# streamr_math_nap.net
KiCad netlist of a schematic drawn in EAGLE
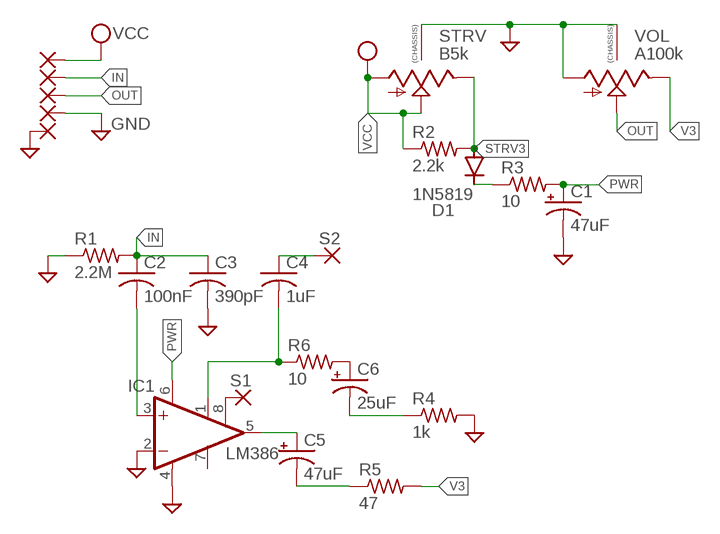
[diagram p0: schematic, sheet 1]

(export (version "E")
  (design (tool "Eeschema 10.0.6"))
  (components
    (comp (ref "C1")
      (value "47uF")
      (footprint "eagle-import:PAN_C_SMD+THRU")
      (libsource (lib "eagle-import") (part "CAP_SMD+THRUPAN_C"))
    )
    (comp (ref "C2")
      (value "100nF")
      (footprint "eagle-import:C0805")
      (libsource (lib "eagle-import") (part "C-USC0805"))
    )
    (comp (ref "C3")
      (value "390pF")
      (footprint "eagle-import:C0805")
      (libsource (lib "eagle-import") (part "C-USC0805"))
    )
    (comp (ref "C4")
      (value "1uF")
      (footprint "eagle-import:C0805")
      (libsource (lib "eagle-import") (part "C-USC0805"))
    )
    (comp (ref "C5")
      (value "47uF")
      (footprint "eagle-import:PAN_C_SMD+THRU")
      (libsource (lib "eagle-import") (part "CAP_SMD+THRUPAN_C"))
    )
    (comp (ref "C6")
      (value "25uF")
      (footprint "eagle-import:PAN_C_SMD+THRU")
      (libsource (lib "eagle-import") (part "CAP_SMD+THRUPAN_C"))
    )
    (comp (ref "D1")
      (value "1N5819")
      (footprint "eagle-import:SOD123")
      (libsource (lib "eagle-import") (part "DIODE-SOD123"))
    )
    (comp (ref "IC1")
      (value "LM386")
      (footprint "eagle-import:SO08")
      (libsource (lib "eagle-import") (part "LM386?-M1"))
    )
    (comp (ref "PAD1")
      (value "1,6/0,8")
      (footprint "eagle-import:1,6_0,8")
      (libsource (lib "eagle-import") (part "1,6/0,8"))
    )
    (comp (ref "PAD2")
      (value "1,6/0,8")
      (footprint "eagle-import:1,6_0,8")
      (libsource (lib "eagle-import") (part "1,6/0,8"))
    )
    (comp (ref "PAD3")
      (value "1,6/0,8")
      (footprint "eagle-import:1,6_0,8")
      (libsource (lib "eagle-import") (part "1,6/0,8"))
    )
    (comp (ref "PAD4")
      (value "1,6/0,8")
      (footprint "eagle-import:1,6_0,8")
      (libsource (lib "eagle-import") (part "1,6/0,8"))
    )
    (comp (ref "PAD5")
      (value "1,6/0,8")
      (footprint "eagle-import:1,6_0,8")
      (libsource (lib "eagle-import") (part "1,6/0,8"))
    )
    (comp (ref "R1")
      (value "2.2M")
      (footprint "eagle-import:R0805")
      (libsource (lib "eagle-import") (part "R-US_R0805"))
    )
    (comp (ref "R2")
      (value "2.2k")
      (footprint "eagle-import:R1206")
      (libsource (lib "eagle-import") (part "R-US_R1206"))
    )
    (comp (ref "R3")
      (value "10")
      (footprint "eagle-import:R1206")
      (libsource (lib "eagle-import") (part "R-US_R1206"))
    )
    (comp (ref "R4")
      (value "1k")
      (footprint "eagle-import:R1206")
      (libsource (lib "eagle-import") (part "R-US_R1206"))
    )
    (comp (ref "R5")
      (value "47")
      (footprint "eagle-import:R1206")
      (libsource (lib "eagle-import") (part "R-US_R1206"))
    )
    (comp (ref "R6")
      (value "10")
      (footprint "eagle-import:R1206")
      (libsource (lib "eagle-import") (part "R-US_R1206"))
    )
    (comp (ref "S1")
      (value "S1")
      (footprint "eagle-import:1,6_0,8")
      (libsource (lib "eagle-import") (part "1,6/0,8"))
    )
    (comp (ref "S2")
      (value "S2")
      (footprint "eagle-import:1,6_0,8")
      (libsource (lib "eagle-import") (part "1,6/0,8"))
    )
    (comp (ref "STRV")
      (value "B5k")
      (footprint "eagle-import:9MM_SNAP-IN_POT")
      (libsource (lib "eagle-import") (part "9MM_SNAP-IN_POT_CHASSIS"))
    )
    (comp (ref "VOL")
      (value "A100k")
      (footprint "eagle-import:9MM_SNAP-IN_POT")
      (libsource (lib "eagle-import") (part "9MM_SNAP-IN_POT_CHASSIS"))
    )
  )
  (nets
    (net (code "1") (name "GND") (class "Default")
      (node (ref "C1") (pin "-") (pinfunction "-_-") (pintype "passive"))
      (node (ref "C1") (pin "--") (pinfunction "-_--") (pintype "passive"))
      (node (ref "C3") (pin "2") (pinfunction "2_2") (pintype "passive"))
      (node (ref "IC1") (pin "2") (pinfunction "-IN_2") (pintype "input"))
      (node (ref "IC1") (pin "4") (pinfunction "GND_4") (pintype "power_in"))
      (node (ref "PAD4") (pin "1") (pinfunction "P_1") (pintype "passive"))
      (node (ref "PAD5") (pin "1") (pinfunction "P_1") (pintype "passive"))
      (node (ref "R1") (pin "1") (pinfunction "1_1") (pintype "passive"))
      (node (ref "R4") (pin "2") (pinfunction "2_2") (pintype "passive"))
      (node (ref "STRV") (pin "CHASSIS1") (pinfunction "P$1_CHASSIS1") (pintype "passive"))
      (node (ref "STRV") (pin "CHASSIS2") (pinfunction "P$1_CHASSIS2") (pintype "passive"))
      (node (ref "VOL") (pin "1") (pinfunction "A_1") (pintype "passive"))
      (node (ref "VOL") (pin "CHASSIS1") (pinfunction "P$1_CHASSIS1") (pintype "passive"))
      (node (ref "VOL") (pin "CHASSIS2") (pinfunction "P$1_CHASSIS2") (pintype "passive"))
    )
    (net (code "2") (name "IN") (class "Default")
      (node (ref "C2") (pin "1") (pinfunction "1_1") (pintype "passive"))
      (node (ref "C3") (pin "1") (pinfunction "1_1") (pintype "passive"))
      (node (ref "PAD2") (pin "1") (pinfunction "P_1") (pintype "passive"))
      (node (ref "R1") (pin "2") (pinfunction "2_2") (pintype "passive"))
    )
    (net (code "3") (name "Net-(C4-Pad2)") (class "Default")
      (node (ref "C4") (pin "2") (pinfunction "2_2") (pintype "passive"))
      (node (ref "IC1") (pin "1") (pinfunction "GAIN_1") (pintype "passive"))
      (node (ref "R6") (pin "1") (pinfunction "1_1") (pintype "passive"))
    )
    (net (code "4") (name "Net-(C5---Pad--)") (class "Default")
      (node (ref "C5") (pin "-") (pinfunction "-_-") (pintype "passive"))
      (node (ref "C5") (pin "--") (pinfunction "-_--") (pintype "passive"))
      (node (ref "R5") (pin "1") (pinfunction "1_1") (pintype "passive"))
    )
    (net (code "5") (name "Net-(C6-+-Pad++)") (class "Default")
      (node (ref "C6") (pin "+") (pinfunction "+_+") (pintype "passive"))
      (node (ref "C6") (pin "++") (pinfunction "+_++") (pintype "passive"))
      (node (ref "R6") (pin "2") (pinfunction "2_2") (pintype "passive"))
    )
    (net (code "6") (name "Net-(C6---Pad--)") (class "Default")
      (node (ref "C6") (pin "-") (pinfunction "-_-") (pintype "passive"))
      (node (ref "C6") (pin "--") (pinfunction "-_--") (pintype "passive"))
      (node (ref "R4") (pin "1") (pinfunction "1_1") (pintype "passive"))
    )
    (net (code "7") (name "Net-(D1-PadC)") (class "Default")
      (node (ref "D1") (pin "C") (pinfunction "C_C") (pintype "passive"))
      (node (ref "R3") (pin "1") (pinfunction "1_1") (pintype "passive"))
    )
    (net (code "8") (name "Net-(IC1-+IN)") (class "Default")
      (node (ref "C2") (pin "2") (pinfunction "2_2") (pintype "passive"))
      (node (ref "IC1") (pin "3") (pinfunction "+IN_3") (pintype "input"))
    )
    (net (code "9") (name "Net-(IC1-OUT)") (class "Default")
      (node (ref "C5") (pin "+") (pinfunction "+_+") (pintype "passive"))
      (node (ref "C5") (pin "++") (pinfunction "+_++") (pintype "passive"))
      (node (ref "IC1") (pin "5") (pinfunction "OUT_5") (pintype "output"))
    )
    (net (code "10") (name "Net-(S1-P)") (class "Default")
      (node (ref "IC1") (pin "8") (pinfunction "GAIN_8") (pintype "passive"))
      (node (ref "S1") (pin "1") (pinfunction "P_1") (pintype "passive"))
    )
    (net (code "11") (name "Net-(S2-P)") (class "Default")
      (node (ref "C4") (pin "1") (pinfunction "1_1") (pintype "passive"))
      (node (ref "S2") (pin "1") (pinfunction "P_1") (pintype "passive"))
    )
    (net (code "12") (name "OUT") (class "Default")
      (node (ref "PAD3") (pin "1") (pinfunction "P_1") (pintype "passive"))
      (node (ref "VOL") (pin "2") (pinfunction "S_2") (pintype "passive"))
    )
    (net (code "13") (name "PWR") (class "Default")
      (node (ref "C1") (pin "+") (pinfunction "+_+") (pintype "passive"))
      (node (ref "C1") (pin "++") (pinfunction "+_++") (pintype "passive"))
      (node (ref "IC1") (pin "6") (pinfunction "VS_6") (pintype "power_in"))
      (node (ref "R3") (pin "2") (pinfunction "2_2") (pintype "passive"))
    )
    (net (code "14") (name "STRV3") (class "Default")
      (node (ref "D1") (pin "A") (pinfunction "A_A") (pintype "passive"))
      (node (ref "R2") (pin "2") (pinfunction "2_2") (pintype "passive"))
      (node (ref "STRV") (pin "3") (pinfunction "E_3") (pintype "passive"))
    )
    (net (code "15") (name "V3") (class "Default")
      (node (ref "R5") (pin "2") (pinfunction "2_2") (pintype "passive"))
      (node (ref "VOL") (pin "3") (pinfunction "E_3") (pintype "passive"))
    )
    (net (code "16") (name "VCC") (class "Default")
      (node (ref "PAD1") (pin "1") (pinfunction "P_1") (pintype "passive"))
      (node (ref "R2") (pin "1") (pinfunction "1_1") (pintype "passive"))
      (node (ref "STRV") (pin "1") (pinfunction "A_1") (pintype "passive"))
      (node (ref "STRV") (pin "2") (pinfunction "S_2") (pintype "passive"))
    )
    (net (code "17") (name "unconnected-(IC1-BYPASS-Pad7)") (class "Default")
      (node (ref "IC1") (pin "7") (pinfunction "BYPASS_7") (pintype "passive"))
    )
  )
)
